# Sensor-ToF.net
KiCad netlist of a schematic drawn in Altium Designer
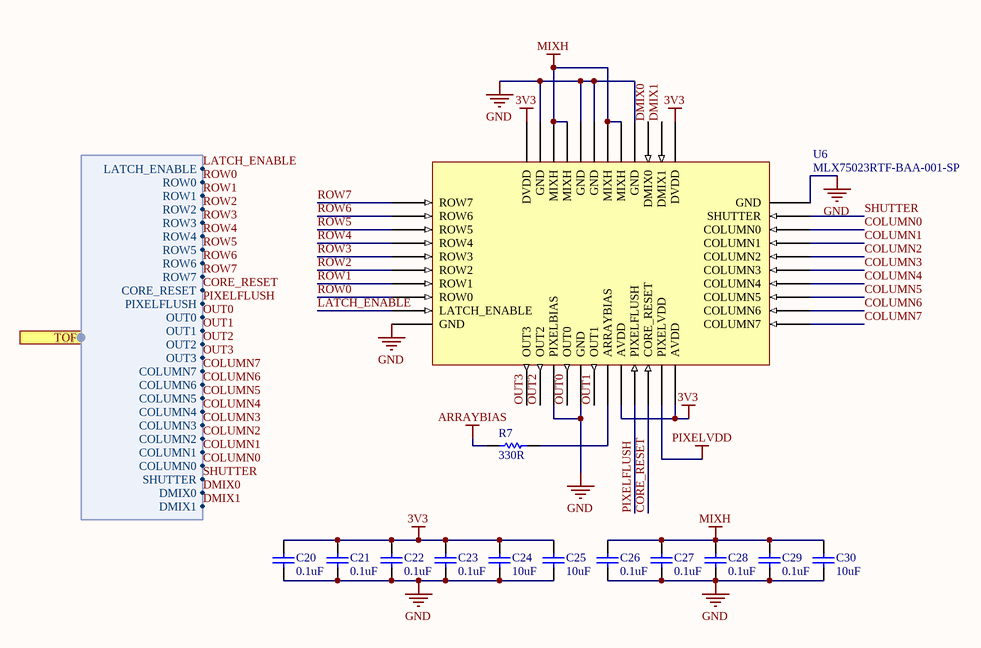
[diagram p0: Sensor-ToF.SchDoc]

(export (version "E")
  (design (tool "Eeschema 10.0.6"))
  (components
    (comp (ref "C20")
      (value "0.1uF")
      (footprint "C0201[0603X30]")
      (description "0.1uF 6.3V 10% 0201 (0603 Metric)")
      (fields (field (name "PARTNUMBER") "GRT033R60J104KE01D") (field (name "MANUFACTURER") "Murata"))
      (libsource (lib "Capacitors") (part "CAP_0.1uF_6.3V_0201_10%"))
    )
    (comp (ref "C21")
      (value "0.1uF")
      (footprint "C0201[0603X30]")
      (description "0.1uF 6.3V 10% 0201 (0603 Metric)")
      (fields (field (name "PARTNUMBER") "GRT033R60J104KE01D") (field (name "MANUFACTURER") "Murata"))
      (libsource (lib "Capacitors") (part "CAP_0.1uF_6.3V_0201_10%"))
    )
    (comp (ref "C22")
      (value "0.1uF")
      (footprint "C0201[0603X30]")
      (description "0.1uF 6.3V 10% 0201 (0603 Metric)")
      (fields (field (name "PARTNUMBER") "GRT033R60J104KE01D") (field (name "MANUFACTURER") "Murata"))
      (libsource (lib "Capacitors") (part "CAP_0.1uF_6.3V_0201_10%"))
    )
    (comp (ref "C23")
      (value "0.1uF")
      (footprint "C0201[0603X30]")
      (description "0.1uF 6.3V 10% 0201 (0603 Metric)")
      (fields (field (name "PARTNUMBER") "GRT033R60J104KE01D") (field (name "MANUFACTURER") "Murata"))
      (libsource (lib "Capacitors") (part "CAP_0.1uF_6.3V_0201_10%"))
    )
    (comp (ref "C24")
      (value "10uF")
      (footprint "C0402[1005X55]")
      (description "10uF 6.3V 20% 0402 (1005 Metric)")
      (fields (field (name "PARTNUMBER") "GRM155R60J106ME44D") (field (name "MANUFACTURER") "Murata"))
      (libsource (lib "Capacitors") (part "CAP_10uF_6.3V_0402_20%"))
    )
    (comp (ref "C25")
      (value "10uF")
      (footprint "C0402[1005X55]")
      (description "10uF 6.3V 20% 0402 (1005 Metric)")
      (fields (field (name "PARTNUMBER") "GRM155R60J106ME44D") (field (name "MANUFACTURER") "Murata"))
      (libsource (lib "Capacitors") (part "CAP_10uF_6.3V_0402_20%"))
    )
    (comp (ref "C26")
      (value "0.1uF")
      (footprint "C0201[0603X30]")
      (description "0.1uF 6.3V 10% 0201 (0603 Metric)")
      (fields (field (name "PARTNUMBER") "GRT033R60J104KE01D") (field (name "MANUFACTURER") "Murata"))
      (libsource (lib "Capacitors") (part "CAP_0.1uF_6.3V_0201_10%"))
    )
    (comp (ref "C27")
      (value "0.1uF")
      (footprint "C0201[0603X30]")
      (description "0.1uF 6.3V 10% 0201 (0603 Metric)")
      (fields (field (name "PARTNUMBER") "GRT033R60J104KE01D") (field (name "MANUFACTURER") "Murata"))
      (libsource (lib "Capacitors") (part "CAP_0.1uF_6.3V_0201_10%"))
    )
    (comp (ref "C28")
      (value "0.1uF")
      (footprint "C0201[0603X30]")
      (description "0.1uF 6.3V 10% 0201 (0603 Metric)")
      (fields (field (name "PARTNUMBER") "GRT033R60J104KE01D") (field (name "MANUFACTURER") "Murata"))
      (libsource (lib "Capacitors") (part "CAP_0.1uF_6.3V_0201_10%"))
    )
    (comp (ref "C29")
      (value "0.1uF")
      (footprint "C0201[0603X30]")
      (description "0.1uF 6.3V 10% 0201 (0603 Metric)")
      (fields (field (name "PARTNUMBER") "GRT033R60J104KE01D") (field (name "MANUFACTURER") "Murata"))
      (libsource (lib "Capacitors") (part "CAP_0.1uF_6.3V_0201_10%"))
    )
    (comp (ref "C30")
      (value "10uF")
      (footprint "C0402[1005X55]")
      (description "10uF 6.3V 20% 0402 (1005 Metric)")
      (fields (field (name "PARTNUMBER") "GRM155R60J106ME44D") (field (name "MANUFACTURER") "Murata"))
      (libsource (lib "Capacitors") (part "CAP_10uF_6.3V_0402_20%"))
    )
    (comp (ref "R7")
      (value "330R")
      (footprint "R0402[1005]")
      (description "330R 0.063W 1% 0402 (1005 Metric)")
      (fields (field (name "MANUFACTURER") "KOA Speer") (field (name "PARTNUMBER") "RK73H1ETTP3300F"))
      (libsource (lib "Resistors") (part "RES_330R_0402_1%_1"))
    )
    (comp (ref "U6")
      (value "MLX75023RTF-BAA-001-SP")
      (footprint "BGA-44")
      (fields (field (name "MANUFACTURER") "Melexis"))
      (libsource (lib "ICs") (part "MLX75023RTF-BAA-001-SP"))
    )
  )
  (nets
    (net (code "2") (name "/COLUMN0") (class "Default")
      (node (ref "U6") (pin "30") (pinfunction "COLUMN0_30") (pintype "input"))
    )
    (net (code "3") (name "/COLUMN1") (class "Default")
      (node (ref "U6") (pin "29") (pinfunction "COLUMN1_29") (pintype "input"))
    )
    (net (code "4") (name "/COLUMN2") (class "Default")
      (node (ref "U6") (pin "28") (pinfunction "COLUMN2_28") (pintype "input"))
    )
    (net (code "5") (name "/COLUMN3") (class "Default")
      (node (ref "U6") (pin "27") (pinfunction "COLUMN3_27") (pintype "input"))
    )
    (net (code "6") (name "/COLUMN4") (class "Default")
      (node (ref "U6") (pin "26") (pinfunction "COLUMN4_26") (pintype "input"))
    )
    (net (code "7") (name "/COLUMN5") (class "Default")
      (node (ref "U6") (pin "25") (pinfunction "COLUMN5_25") (pintype "input"))
    )
    (net (code "8") (name "/COLUMN6") (class "Default")
      (node (ref "U6") (pin "24") (pinfunction "COLUMN6_24") (pintype "input"))
    )
    (net (code "9") (name "/COLUMN7") (class "Default")
      (node (ref "U6") (pin "23") (pinfunction "COLUMN7_23") (pintype "input"))
    )
    (net (code "10") (name "/CORE_RESET") (class "Default")
      (node (ref "U6") (pin "20") (pinfunction "CORE_RESET_20") (pintype "input"))
    )
    (net (code "11") (name "/DMIX0") (class "Default")
      (node (ref "U6") (pin "35") (pinfunction "DMIX0_35") (pintype "input"))
    )
    (net (code "12") (name "/DMIX1") (class "Default")
      (node (ref "U6") (pin "34") (pinfunction "DMIX1_34") (pintype "input"))
    )
    (net (code "13") (name "/LATCH_ENABLE") (class "Default")
      (node (ref "U6") (pin "9") (pinfunction "LATCH_ENABLE_9") (pintype "input"))
    )
    (net (code "14") (name "/OUT0") (class "Default")
      (node (ref "U6") (pin "14") (pinfunction "OUT0_14") (pintype "output"))
    )
    (net (code "15") (name "/OUT1") (class "Default")
      (node (ref "U6") (pin "16") (pinfunction "OUT1_16") (pintype "output"))
    )
    (net (code "16") (name "/OUT2") (class "Default")
      (node (ref "U6") (pin "12") (pinfunction "OUT2_12") (pintype "output"))
    )
    (net (code "17") (name "/OUT3") (class "Default")
      (node (ref "U6") (pin "11") (pinfunction "OUT3_11") (pintype "output"))
    )
    (net (code "18") (name "/PIXELFLUSH") (class "Default")
      (node (ref "U6") (pin "19") (pinfunction "PIXELFLUSH_19") (pintype "input"))
    )
    (net (code "19") (name "/ROW0") (class "Default")
      (node (ref "U6") (pin "8") (pinfunction "ROW0_8") (pintype "input"))
    )
    (net (code "20") (name "/ROW1") (class "Default")
      (node (ref "U6") (pin "7") (pinfunction "ROW1_7") (pintype "input"))
    )
    (net (code "21") (name "/ROW2") (class "Default")
      (node (ref "U6") (pin "6") (pinfunction "ROW2_6") (pintype "input"))
    )
    (net (code "22") (name "/ROW3") (class "Default")
      (node (ref "U6") (pin "5") (pinfunction "ROW3_5") (pintype "input"))
    )
    (net (code "23") (name "/ROW4") (class "Default")
      (node (ref "U6") (pin "4") (pinfunction "ROW4_4") (pintype "input"))
    )
    (net (code "24") (name "/ROW5") (class "Default")
      (node (ref "U6") (pin "3") (pinfunction "ROW5_3") (pintype "input"))
    )
    (net (code "25") (name "/ROW6") (class "Default")
      (node (ref "U6") (pin "2") (pinfunction "ROW6_2") (pintype "input"))
    )
    (net (code "26") (name "/ROW7") (class "Default")
      (node (ref "U6") (pin "1") (pinfunction "ROW7_1") (pintype "input"))
    )
    (net (code "27") (name "/SHUTTER") (class "Default")
      (node (ref "U6") (pin "31") (pinfunction "SHUTTER_31") (pintype "input"))
    )
    (net (code "29") (name "3V3") (class "Default")
      (node (ref "C20") (pin "2") (pinfunction "2_2") (pintype "passive"))
      (node (ref "C21") (pin "2") (pinfunction "2_2") (pintype "passive"))
      (node (ref "C22") (pin "2") (pinfunction "2_2") (pintype "passive"))
      (node (ref "C23") (pin "2") (pinfunction "2_2") (pintype "passive"))
      (node (ref "C24") (pin "2") (pinfunction "2_2") (pintype "passive"))
      (node (ref "C25") (pin "2") (pinfunction "2_2") (pintype "passive"))
      (node (ref "U6") (pin "18") (pinfunction "AVDD_18") (pintype "power_in"))
      (node (ref "U6") (pin "22") (pinfunction "AVDD_22") (pintype "power_in"))
      (node (ref "U6") (pin "33") (pinfunction "DVDD_33") (pintype "power_in"))
      (node (ref "U6") (pin "44") (pinfunction "DVDD_44") (pintype "power_in"))
    )
    (net (code "30") (name "ARRAYBIAS") (class "Default")
      (node (ref "R7") (pin "1") (pinfunction "1_1") (pintype "passive"))
    )
    (net (code "31") (name "GND") (class "Default")
      (node (ref "C20") (pin "1") (pinfunction "1_1") (pintype "passive"))
      (node (ref "C21") (pin "1") (pinfunction "1_1") (pintype "passive"))
      (node (ref "C22") (pin "1") (pinfunction "1_1") (pintype "passive"))
      (node (ref "C23") (pin "1") (pinfunction "1_1") (pintype "passive"))
      (node (ref "C24") (pin "1") (pinfunction "1_1") (pintype "passive"))
      (node (ref "C25") (pin "1") (pinfunction "1_1") (pintype "passive"))
      (node (ref "C26") (pin "1") (pinfunction "1_1") (pintype "passive"))
      (node (ref "C27") (pin "1") (pinfunction "1_1") (pintype "passive"))
      (node (ref "C28") (pin "1") (pinfunction "1_1") (pintype "passive"))
      (node (ref "C29") (pin "1") (pinfunction "1_1") (pintype "passive"))
      (node (ref "C30") (pin "1") (pinfunction "1_1") (pintype "passive"))
      (node (ref "U6") (pin "10") (pinfunction "GND_10") (pintype "power_in"))
      (node (ref "U6") (pin "13") (pinfunction "PIXELBIAS_13") (pintype "passive"))
      (node (ref "U6") (pin "15") (pinfunction "GND_15") (pintype "power_in"))
      (node (ref "U6") (pin "32") (pinfunction "GND_32") (pintype "power_in"))
      (node (ref "U6") (pin "36") (pinfunction "GND_36") (pintype "power_in"))
      (node (ref "U6") (pin "39") (pinfunction "GND_39") (pintype "power_in"))
      (node (ref "U6") (pin "40") (pinfunction "GND_40") (pintype "power_in"))
      (node (ref "U6") (pin "43") (pinfunction "GND_43") (pintype "power_in"))
    )
    (net (code "32") (name "MIXH") (class "Default")
      (node (ref "C26") (pin "2") (pinfunction "2_2") (pintype "passive"))
      (node (ref "C27") (pin "2") (pinfunction "2_2") (pintype "passive"))
      (node (ref "C28") (pin "2") (pinfunction "2_2") (pintype "passive"))
      (node (ref "C29") (pin "2") (pinfunction "2_2") (pintype "passive"))
      (node (ref "C30") (pin "2") (pinfunction "2_2") (pintype "passive"))
      (node (ref "U6") (pin "37") (pinfunction "MIXH_37") (pintype "power_in"))
      (node (ref "U6") (pin "38") (pinfunction "MIXH_38") (pintype "power_in"))
      (node (ref "U6") (pin "41") (pinfunction "MIXH_41") (pintype "power_in"))
      (node (ref "U6") (pin "42") (pinfunction "MIXH_42") (pintype "power_in"))
    )
    (net (code "33") (name "Net-(U6-ARRAYBIAS)") (class "Default")
      (node (ref "R7") (pin "2") (pinfunction "2_2") (pintype "passive"))
      (node (ref "U6") (pin "17") (pinfunction "ARRAYBIAS_17") (pintype "passive"))
    )
    (net (code "34") (name "PIXELVDD") (class "Default")
      (node (ref "U6") (pin "21") (pinfunction "PIXELVDD_21") (pintype "power_in"))
    )
  )
)
